# Led_CTR.net
KiCad netlist of a schematic drawn in Altium Designer
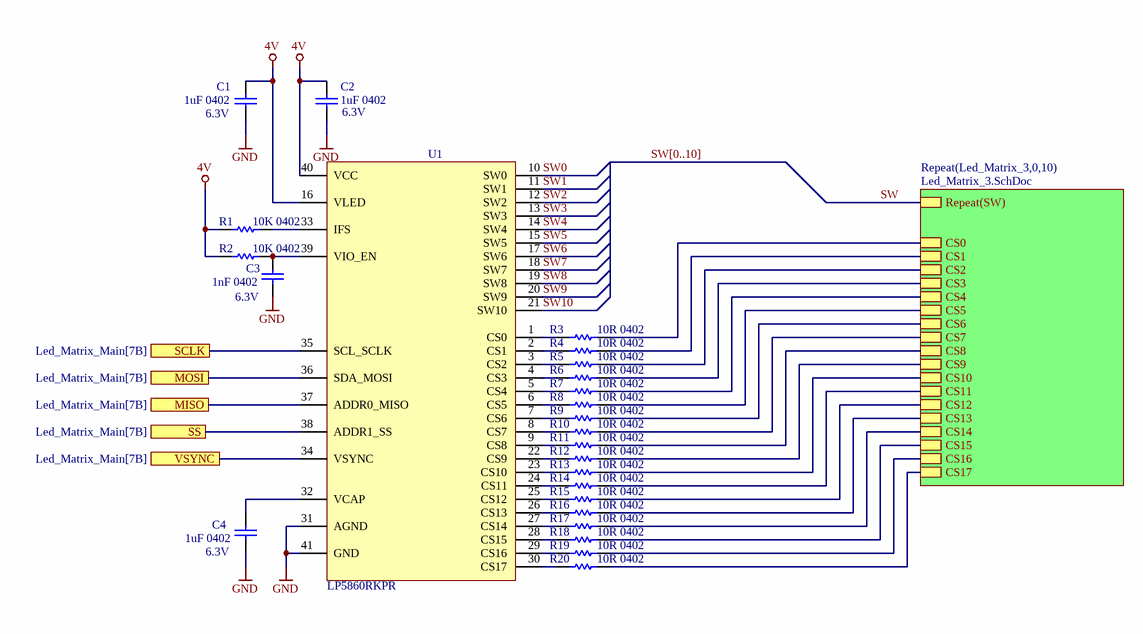
[diagram p0: Led_CTR.SchDoc]

(export (version "E")
  (design (tool "Eeschema 10.0.6"))
  (components
    (comp (ref "C1")
      (value "1uF 0402")
      (footprint "CAPC0402(1005)70")
      (description "Surface Mount Ceramic Multilayer Capacitor 1uF, ± 20%, X5R, 6.3V, 0402")
      (fields
        (field (name "TOLERANCE") "20%")
        (field (name "MANUFACTURER") "Murata")
        (field (name "VOLTAGE") "6.3V")
      )
      (libsource (lib "Led_Matrix") (part "C_1uF_0402_6.3V_X5R"))
    )
    (comp (ref "C2")
      (value "1uF 0402")
      (footprint "CAPC0402(1005)70")
      (description "Surface Mount Ceramic Multilayer Capacitor 1uF, ± 20%, X5R, 6.3V, 0402")
      (fields
        (field (name "TOLERANCE") "20%")
        (field (name "MANUFACTURER") "Murata")
        (field (name "VOLTAGE") "6.3V")
      )
      (libsource (lib "Led_Matrix") (part "C_1uF_0402_6.3V_X5R"))
    )
    (comp (ref "C3")
      (value "1nF 0402")
      (footprint "CAPC0402(1005)70")
      (description "Surface Mount Ceramic Multilayer Capacitor 1nF, ± 10%, X7R, 6.3V, 0402")
      (fields
        (field (name "TOLERANCE") "10%")
        (field (name "MANUFACTURER") "Murata")
        (field (name "VOLTAGE") "6.3V")
      )
      (libsource (lib "Led_Matrix") (part "C_1nF_0402_6.3V_X7R"))
    )
    (comp (ref "C4")
      (value "1uF 0402")
      (footprint "CAPC0402(1005)70")
      (description "Surface Mount Ceramic Multilayer Capacitor 1uF, ± 20%, X5R, 6.3V, 0402")
      (fields
        (field (name "TOLERANCE") "20%")
        (field (name "MANUFACTURER") "Murata")
        (field (name "VOLTAGE") "6.3V")
      )
      (libsource (lib "Led_Matrix") (part "C_1uF_0402_6.3V_X5R"))
    )
    (comp (ref "R1")
      (value "10K 0402")
      (footprint "RESC0402(1005)")
      (description "Resistor: thick film; SMD; 0402; 10KΩ; 63mW; ±1%; -55÷155°C")
      (fields (field (name "TOLERANCE") "1%") (field (name "MANUFACTURER") "Vishay"))
      (libsource (lib "Led_Matrix") (part "R_10K_0402_1%"))
    )
    (comp (ref "R2")
      (value "10K 0402")
      (footprint "RESC0402(1005)")
      (description "Resistor: thick film; SMD; 0402; 10KΩ; 63mW; ±1%; -55÷155°C")
      (fields (field (name "TOLERANCE") "1%") (field (name "MANUFACTURER") "Vishay"))
      (libsource (lib "Led_Matrix") (part "R_10K_0402_1%"))
    )
    (comp (ref "R3")
      (value "10R 0402")
      (footprint "RESC0402(1005)")
      (description "Resistor: thick film; SMD; 0402; 10Ω; 63mW; ±1%; -55÷155°C")
      (fields
        (field (name "MANUFACTURER") "Royal Electronic Factory")
        (field (name "MANUFACTURER PART NUMBER") "0402WGF100JTCE")
      )
      (libsource (lib "Led_Matrix") (part "R_10R_0402_1%"))
    )
    (comp (ref "R4")
      (value "10R 0402")
      (footprint "RESC0402(1005)")
      (description "Resistor: thick film; SMD; 0402; 10Ω; 63mW; ±1%; -55÷155°C")
      (fields
        (field (name "MANUFACTURER") "Royal Electronic Factory")
        (field (name "MANUFACTURER PART NUMBER") "0402WGF100JTCE")
      )
      (libsource (lib "Led_Matrix") (part "R_10R_0402_1%"))
    )
    (comp (ref "R5")
      (value "10R 0402")
      (footprint "RESC0402(1005)")
      (description "Resistor: thick film; SMD; 0402; 10Ω; 63mW; ±1%; -55÷155°C")
      (fields
        (field (name "MANUFACTURER") "Royal Electronic Factory")
        (field (name "MANUFACTURER PART NUMBER") "0402WGF100JTCE")
      )
      (libsource (lib "Led_Matrix") (part "R_10R_0402_1%"))
    )
    (comp (ref "R6")
      (value "10R 0402")
      (footprint "RESC0402(1005)")
      (description "Resistor: thick film; SMD; 0402; 10Ω; 63mW; ±1%; -55÷155°C")
      (fields
        (field (name "MANUFACTURER") "Royal Electronic Factory")
        (field (name "MANUFACTURER PART NUMBER") "0402WGF100JTCE")
      )
      (libsource (lib "Led_Matrix") (part "R_10R_0402_1%"))
    )
    (comp (ref "R7")
      (value "10R 0402")
      (footprint "RESC0402(1005)")
      (description "Resistor: thick film; SMD; 0402; 10Ω; 63mW; ±1%; -55÷155°C")
      (fields
        (field (name "MANUFACTURER") "Royal Electronic Factory")
        (field (name "MANUFACTURER PART NUMBER") "0402WGF100JTCE")
      )
      (libsource (lib "Led_Matrix") (part "R_10R_0402_1%"))
    )
    (comp (ref "R8")
      (value "10R 0402")
      (footprint "RESC0402(1005)")
      (description "Resistor: thick film; SMD; 0402; 10Ω; 63mW; ±1%; -55÷155°C")
      (fields
        (field (name "MANUFACTURER") "Royal Electronic Factory")
        (field (name "MANUFACTURER PART NUMBER") "0402WGF100JTCE")
      )
      (libsource (lib "Led_Matrix") (part "R_10R_0402_1%"))
    )
    (comp (ref "R9")
      (value "10R 0402")
      (footprint "RESC0402(1005)")
      (description "Resistor: thick film; SMD; 0402; 10Ω; 63mW; ±1%; -55÷155°C")
      (fields
        (field (name "MANUFACTURER") "Royal Electronic Factory")
        (field (name "MANUFACTURER PART NUMBER") "0402WGF100JTCE")
      )
      (libsource (lib "Led_Matrix") (part "R_10R_0402_1%"))
    )
    (comp (ref "R10")
      (value "10R 0402")
      (footprint "RESC0402(1005)")
      (description "Resistor: thick film; SMD; 0402; 10Ω; 63mW; ±1%; -55÷155°C")
      (fields
        (field (name "MANUFACTURER") "Royal Electronic Factory")
        (field (name "MANUFACTURER PART NUMBER") "0402WGF100JTCE")
      )
      (libsource (lib "Led_Matrix") (part "R_10R_0402_1%"))
    )
    (comp (ref "R11")
      (value "10R 0402")
      (footprint "RESC0402(1005)")
      (description "Resistor: thick film; SMD; 0402; 10Ω; 63mW; ±1%; -55÷155°C")
      (fields
        (field (name "MANUFACTURER") "Royal Electronic Factory")
        (field (name "MANUFACTURER PART NUMBER") "0402WGF100JTCE")
      )
      (libsource (lib "Led_Matrix") (part "R_10R_0402_1%"))
    )
    (comp (ref "R12")
      (value "10R 0402")
      (footprint "RESC0402(1005)")
      (description "Resistor: thick film; SMD; 0402; 10Ω; 63mW; ±1%; -55÷155°C")
      (fields
        (field (name "MANUFACTURER") "Royal Electronic Factory")
        (field (name "MANUFACTURER PART NUMBER") "0402WGF100JTCE")
      )
      (libsource (lib "Led_Matrix") (part "R_10R_0402_1%"))
    )
    (comp (ref "R13")
      (value "10R 0402")
      (footprint "RESC0402(1005)")
      (description "Resistor: thick film; SMD; 0402; 10Ω; 63mW; ±1%; -55÷155°C")
      (fields
        (field (name "MANUFACTURER") "Royal Electronic Factory")
        (field (name "MANUFACTURER PART NUMBER") "0402WGF100JTCE")
      )
      (libsource (lib "Led_Matrix") (part "R_10R_0402_1%"))
    )
    (comp (ref "R14")
      (value "10R 0402")
      (footprint "RESC0402(1005)")
      (description "Resistor: thick film; SMD; 0402; 10Ω; 63mW; ±1%; -55÷155°C")
      (fields
        (field (name "MANUFACTURER") "Royal Electronic Factory")
        (field (name "MANUFACTURER PART NUMBER") "0402WGF100JTCE")
      )
      (libsource (lib "Led_Matrix") (part "R_10R_0402_1%"))
    )
    (comp (ref "R15")
      (value "10R 0402")
      (footprint "RESC0402(1005)")
      (description "Resistor: thick film; SMD; 0402; 10Ω; 63mW; ±1%; -55÷155°C")
      (fields
        (field (name "MANUFACTURER") "Royal Electronic Factory")
        (field (name "MANUFACTURER PART NUMBER") "0402WGF100JTCE")
      )
      (libsource (lib "Led_Matrix") (part "R_10R_0402_1%"))
    )
    (comp (ref "R16")
      (value "10R 0402")
      (footprint "RESC0402(1005)")
      (description "Resistor: thick film; SMD; 0402; 10Ω; 63mW; ±1%; -55÷155°C")
      (fields
        (field (name "MANUFACTURER") "Royal Electronic Factory")
        (field (name "MANUFACTURER PART NUMBER") "0402WGF100JTCE")
      )
      (libsource (lib "Led_Matrix") (part "R_10R_0402_1%"))
    )
    (comp (ref "R17")
      (value "10R 0402")
      (footprint "RESC0402(1005)")
      (description "Resistor: thick film; SMD; 0402; 10Ω; 63mW; ±1%; -55÷155°C")
      (fields
        (field (name "MANUFACTURER") "Royal Electronic Factory")
        (field (name "MANUFACTURER PART NUMBER") "0402WGF100JTCE")
      )
      (libsource (lib "Led_Matrix") (part "R_10R_0402_1%"))
    )
    (comp (ref "R18")
      (value "10R 0402")
      (footprint "RESC0402(1005)")
      (description "Resistor: thick film; SMD; 0402; 10Ω; 63mW; ±1%; -55÷155°C")
      (fields
        (field (name "MANUFACTURER") "Royal Electronic Factory")
        (field (name "MANUFACTURER PART NUMBER") "0402WGF100JTCE")
      )
      (libsource (lib "Led_Matrix") (part "R_10R_0402_1%"))
    )
    (comp (ref "R19")
      (value "10R 0402")
      (footprint "RESC0402(1005)")
      (description "Resistor: thick film; SMD; 0402; 10Ω; 63mW; ±1%; -55÷155°C")
      (fields
        (field (name "MANUFACTURER") "Royal Electronic Factory")
        (field (name "MANUFACTURER PART NUMBER") "0402WGF100JTCE")
      )
      (libsource (lib "Led_Matrix") (part "R_10R_0402_1%"))
    )
    (comp (ref "R20")
      (value "10R 0402")
      (footprint "RESC0402(1005)")
      (description "Resistor: thick film; SMD; 0402; 10Ω; 63mW; ±1%; -55÷155°C")
      (fields
        (field (name "MANUFACTURER") "Royal Electronic Factory")
        (field (name "MANUFACTURER PART NUMBER") "0402WGF100JTCE")
      )
      (libsource (lib "Led_Matrix") (part "R_10R_0402_1%"))
    )
    (comp (ref "U1")
      (value "LP5860RKPR")
      (footprint "VQFN-40")
      (description "11 × 18 LED matrix driver with 8-bit analog and 8-/16-bit PWM dimming 40-VQFN -40 to 85")
      (fields (field (name "MANUFACTURER") "Texas Instruments"))
      (libsource (lib "Led_Matrix") (part "IC_LED_DRIVER_LP5860RKPR"))
    )
  )
  (nets
    (net (code "1") (name "/CS0") (class "Default")
      (node (ref "R3") (pin "2") (pinfunction "2_2") (pintype "passive"))
    )
    (net (code "2") (name "/CS1") (class "Default")
      (node (ref "R4") (pin "2") (pinfunction "2_2") (pintype "passive"))
    )
    (net (code "3") (name "/CS2") (class "Default")
      (node (ref "R5") (pin "2") (pinfunction "2_2") (pintype "passive"))
    )
    (net (code "4") (name "/CS3") (class "Default")
      (node (ref "R6") (pin "2") (pinfunction "2_2") (pintype "passive"))
    )
    (net (code "5") (name "/CS4") (class "Default")
      (node (ref "R7") (pin "2") (pinfunction "2_2") (pintype "passive"))
    )
    (net (code "6") (name "/CS5") (class "Default")
      (node (ref "R8") (pin "2") (pinfunction "2_2") (pintype "passive"))
    )
    (net (code "7") (name "/CS6") (class "Default")
      (node (ref "R9") (pin "2") (pinfunction "2_2") (pintype "passive"))
    )
    (net (code "8") (name "/CS7") (class "Default")
      (node (ref "R10") (pin "2") (pinfunction "2_2") (pintype "passive"))
    )
    (net (code "9") (name "/CS8") (class "Default")
      (node (ref "R11") (pin "2") (pinfunction "2_2") (pintype "passive"))
    )
    (net (code "10") (name "/CS9") (class "Default")
      (node (ref "R12") (pin "2") (pinfunction "2_2") (pintype "passive"))
    )
    (net (code "11") (name "/CS10") (class "Default")
      (node (ref "R13") (pin "2") (pinfunction "2_2") (pintype "passive"))
    )
    (net (code "12") (name "/CS11") (class "Default")
      (node (ref "R14") (pin "2") (pinfunction "2_2") (pintype "passive"))
    )
    (net (code "13") (name "/CS12") (class "Default")
      (node (ref "R15") (pin "2") (pinfunction "2_2") (pintype "passive"))
    )
    (net (code "14") (name "/CS13") (class "Default")
      (node (ref "R16") (pin "2") (pinfunction "2_2") (pintype "passive"))
    )
    (net (code "15") (name "/CS14") (class "Default")
      (node (ref "R17") (pin "2") (pinfunction "2_2") (pintype "passive"))
    )
    (net (code "16") (name "/CS15") (class "Default")
      (node (ref "R18") (pin "2") (pinfunction "2_2") (pintype "passive"))
    )
    (net (code "17") (name "/CS16") (class "Default")
      (node (ref "R19") (pin "2") (pinfunction "2_2") (pintype "passive"))
    )
    (net (code "18") (name "/CS17") (class "Default")
      (node (ref "R20") (pin "2") (pinfunction "2_2") (pintype "passive"))
    )
    (net (code "19") (name "/MISO") (class "Default")
      (node (ref "U1") (pin "37") (pinfunction "ADDR0_MISO_37") (pintype "passive"))
    )
    (net (code "20") (name "/MOSI") (class "Default")
      (node (ref "U1") (pin "36") (pinfunction "SDA_MOSI_36") (pintype "passive"))
    )
    (net (code "21") (name "/SCLK") (class "Default")
      (node (ref "U1") (pin "35") (pinfunction "SCL_SCLK_35") (pintype "passive"))
    )
    (net (code "22") (name "/SS") (class "Default")
      (node (ref "U1") (pin "38") (pinfunction "ADDR1_SS_38") (pintype "passive"))
    )
    (net (code "24") (name "/SW0") (class "Default")
      (node (ref "U1") (pin "10") (pinfunction "SW0_10") (pintype "passive"))
    )
    (net (code "25") (name "/SW1") (class "Default")
      (node (ref "U1") (pin "11") (pinfunction "SW1_11") (pintype "passive"))
    )
    (net (code "26") (name "/SW2") (class "Default")
      (node (ref "U1") (pin "12") (pinfunction "SW2_12") (pintype "passive"))
    )
    (net (code "27") (name "/SW3") (class "Default")
      (node (ref "U1") (pin "13") (pinfunction "SW3_13") (pintype "passive"))
    )
    (net (code "28") (name "/SW4") (class "Default")
      (node (ref "U1") (pin "14") (pinfunction "SW4_14") (pintype "passive"))
    )
    (net (code "29") (name "/SW5") (class "Default")
      (node (ref "U1") (pin "15") (pinfunction "SW5_15") (pintype "passive"))
    )
    (net (code "30") (name "/SW6") (class "Default")
      (node (ref "U1") (pin "17") (pinfunction "SW6_17") (pintype "passive"))
    )
    (net (code "31") (name "/SW7") (class "Default")
      (node (ref "U1") (pin "18") (pinfunction "SW7_18") (pintype "passive"))
    )
    (net (code "32") (name "/SW8") (class "Default")
      (node (ref "U1") (pin "19") (pinfunction "SW8_19") (pintype "passive"))
    )
    (net (code "33") (name "/SW9") (class "Default")
      (node (ref "U1") (pin "20") (pinfunction "SW9_20") (pintype "passive"))
    )
    (net (code "34") (name "/SW10") (class "Default")
      (node (ref "U1") (pin "21") (pinfunction "SW10_21") (pintype "passive"))
    )
    (net (code "36") (name "/VSYNC") (class "Default")
      (node (ref "U1") (pin "34") (pinfunction "VSYNC_34") (pintype "passive"))
    )
    (net (code "37") (name "4V") (class "Default")
      (node (ref "C1") (pin "2") (pinfunction "2_2") (pintype "passive"))
      (node (ref "C2") (pin "2") (pinfunction "2_2") (pintype "passive"))
      (node (ref "R1") (pin "1") (pinfunction "1_1") (pintype "passive"))
      (node (ref "R2") (pin "1") (pinfunction "1_1") (pintype "passive"))
      (node (ref "U1") (pin "16") (pinfunction "VLED_16") (pintype "passive"))
      (node (ref "U1") (pin "40") (pinfunction "VCC_40") (pintype "passive"))
    )
    (net (code "38") (name "GND") (class "Default")
      (node (ref "C1") (pin "1") (pinfunction "1_1") (pintype "passive"))
      (node (ref "C2") (pin "1") (pinfunction "1_1") (pintype "passive"))
      (node (ref "C3") (pin "2") (pinfunction "2_2") (pintype "passive"))
      (node (ref "C4") (pin "1") (pinfunction "1_1") (pintype "passive"))
      (node (ref "U1") (pin "31") (pinfunction "AGND_31") (pintype "passive"))
      (node (ref "U1") (pin "41") (pinfunction "GND_41") (pintype "passive"))
    )
    (net (code "39") (name "Net-(U1-CS0)") (class "Default")
      (node (ref "R3") (pin "1") (pinfunction "1_1") (pintype "passive"))
      (node (ref "U1") (pin "1") (pinfunction "CS0_1") (pintype "passive"))
    )
    (net (code "40") (name "Net-(U1-CS1)") (class "Default")
      (node (ref "R4") (pin "1") (pinfunction "1_1") (pintype "passive"))
      (node (ref "U1") (pin "2") (pinfunction "CS1_2") (pintype "passive"))
    )
    (net (code "41") (name "Net-(U1-CS2)") (class "Default")
      (node (ref "R5") (pin "1") (pinfunction "1_1") (pintype "passive"))
      (node (ref "U1") (pin "3") (pinfunction "CS2_3") (pintype "passive"))
    )
    (net (code "42") (name "Net-(U1-CS3)") (class "Default")
      (node (ref "R6") (pin "1") (pinfunction "1_1") (pintype "passive"))
      (node (ref "U1") (pin "4") (pinfunction "CS3_4") (pintype "passive"))
    )
    (net (code "43") (name "Net-(U1-CS4)") (class "Default")
      (node (ref "R7") (pin "1") (pinfunction "1_1") (pintype "passive"))
      (node (ref "U1") (pin "5") (pinfunction "CS4_5") (pintype "passive"))
    )
    (net (code "44") (name "Net-(U1-CS5)") (class "Default")
      (node (ref "R8") (pin "1") (pinfunction "1_1") (pintype "passive"))
      (node (ref "U1") (pin "6") (pinfunction "CS5_6") (pintype "passive"))
    )
    (net (code "45") (name "Net-(U1-CS6)") (class "Default")
      (node (ref "R9") (pin "1") (pinfunction "1_1") (pintype "passive"))
      (node (ref "U1") (pin "7") (pinfunction "CS6_7") (pintype "passive"))
    )
    (net (code "46") (name "Net-(U1-CS7)") (class "Default")
      (node (ref "R10") (pin "1") (pinfunction "1_1") (pintype "passive"))
      (node (ref "U1") (pin "8") (pinfunction "CS7_8") (pintype "passive"))
    )
    (net (code "47") (name "Net-(U1-CS8)") (class "Default")
      (node (ref "R11") (pin "1") (pinfunction "1_1") (pintype "passive"))
      (node (ref "U1") (pin "9") (pinfunction "CS8_9") (pintype "passive"))
    )
    (net (code "48") (name "Net-(U1-CS9)") (class "Default")
      (node (ref "R12") (pin "1") (pinfunction "1_1") (pintype "passive"))
      (node (ref "U1") (pin "22") (pinfunction "CS9_22") (pintype "passive"))
    )
    (net (code "49") (name "Net-(U1-CS10)") (class "Default")
      (node (ref "R13") (pin "1") (pinfunction "1_1") (pintype "passive"))
      (node (ref "U1") (pin "23") (pinfunction "CS10_23") (pintype "passive"))
    )
    (net (code "50") (name "Net-(U1-CS11)") (class "Default")
      (node (ref "R14") (pin "1") (pinfunction "1_1") (pintype "passive"))
      (node (ref "U1") (pin "24") (pinfunction "CS11_24") (pintype "passive"))
    )
    (net (code "51") (name "Net-(U1-CS12)") (class "Default")
      (node (ref "R15") (pin "1") (pinfunction "1_1") (pintype "passive"))
      (node (ref "U1") (pin "25") (pinfunction "CS12_25") (pintype "passive"))
    )
    (net (code "52") (name "Net-(U1-CS13)") (class "Default")
      (node (ref "R16") (pin "1") (pinfunction "1_1") (pintype "passive"))
      (node (ref "U1") (pin "26") (pinfunction "CS13_26") (pintype "passive"))
    )
    (net (code "53") (name "Net-(U1-CS14)") (class "Default")
      (node (ref "R17") (pin "1") (pinfunction "1_1") (pintype "passive"))
      (node (ref "U1") (pin "27") (pinfunction "CS14_27") (pintype "passive"))
    )
    (net (code "54") (name "Net-(U1-CS15)") (class "Default")
      (node (ref "R18") (pin "1") (pinfunction "1_1") (pintype "passive"))
      (node (ref "U1") (pin "28") (pinfunction "CS15_28") (pintype "passive"))
    )
    (net (code "55") (name "Net-(U1-CS16)") (class "Default")
      (node (ref "R19") (pin "1") (pinfunction "1_1") (pintype "passive"))
      (node (ref "U1") (pin "29") (pinfunction "CS16_29") (pintype "passive"))
    )
    (net (code "56") (name "Net-(U1-CS17)") (class "Default")
      (node (ref "R20") (pin "1") (pinfunction "1_1") (pintype "passive"))
      (node (ref "U1") (pin "30") (pinfunction "CS17_30") (pintype "passive"))
    )
    (net (code "57") (name "Net-(U1-IFS)") (class "Default")
      (node (ref "R1") (pin "2") (pinfunction "2_2") (pintype "passive"))
      (node (ref "U1") (pin "33") (pinfunction "IFS_33") (pintype "passive"))
    )
    (net (code "58") (name "Net-(U1-VCAP)") (class "Default")
      (node (ref "C4") (pin "2") (pinfunction "2_2") (pintype "passive"))
      (node (ref "U1") (pin "32") (pinfunction "VCAP_32") (pintype "passive"))
    )
    (net (code "59") (name "Net-(U1-VIO_EN)") (class "Default")
      (node (ref "C3") (pin "1") (pinfunction "1_1") (pintype "passive"))
      (node (ref "R2") (pin "2") (pinfunction "2_2") (pintype "passive"))
      (node (ref "U1") (pin "39") (pinfunction "VIO_EN_39") (pintype "passive"))
    )
  )
)
